# DI.net
KiCad netlist of a schematic drawn in Altium Designer
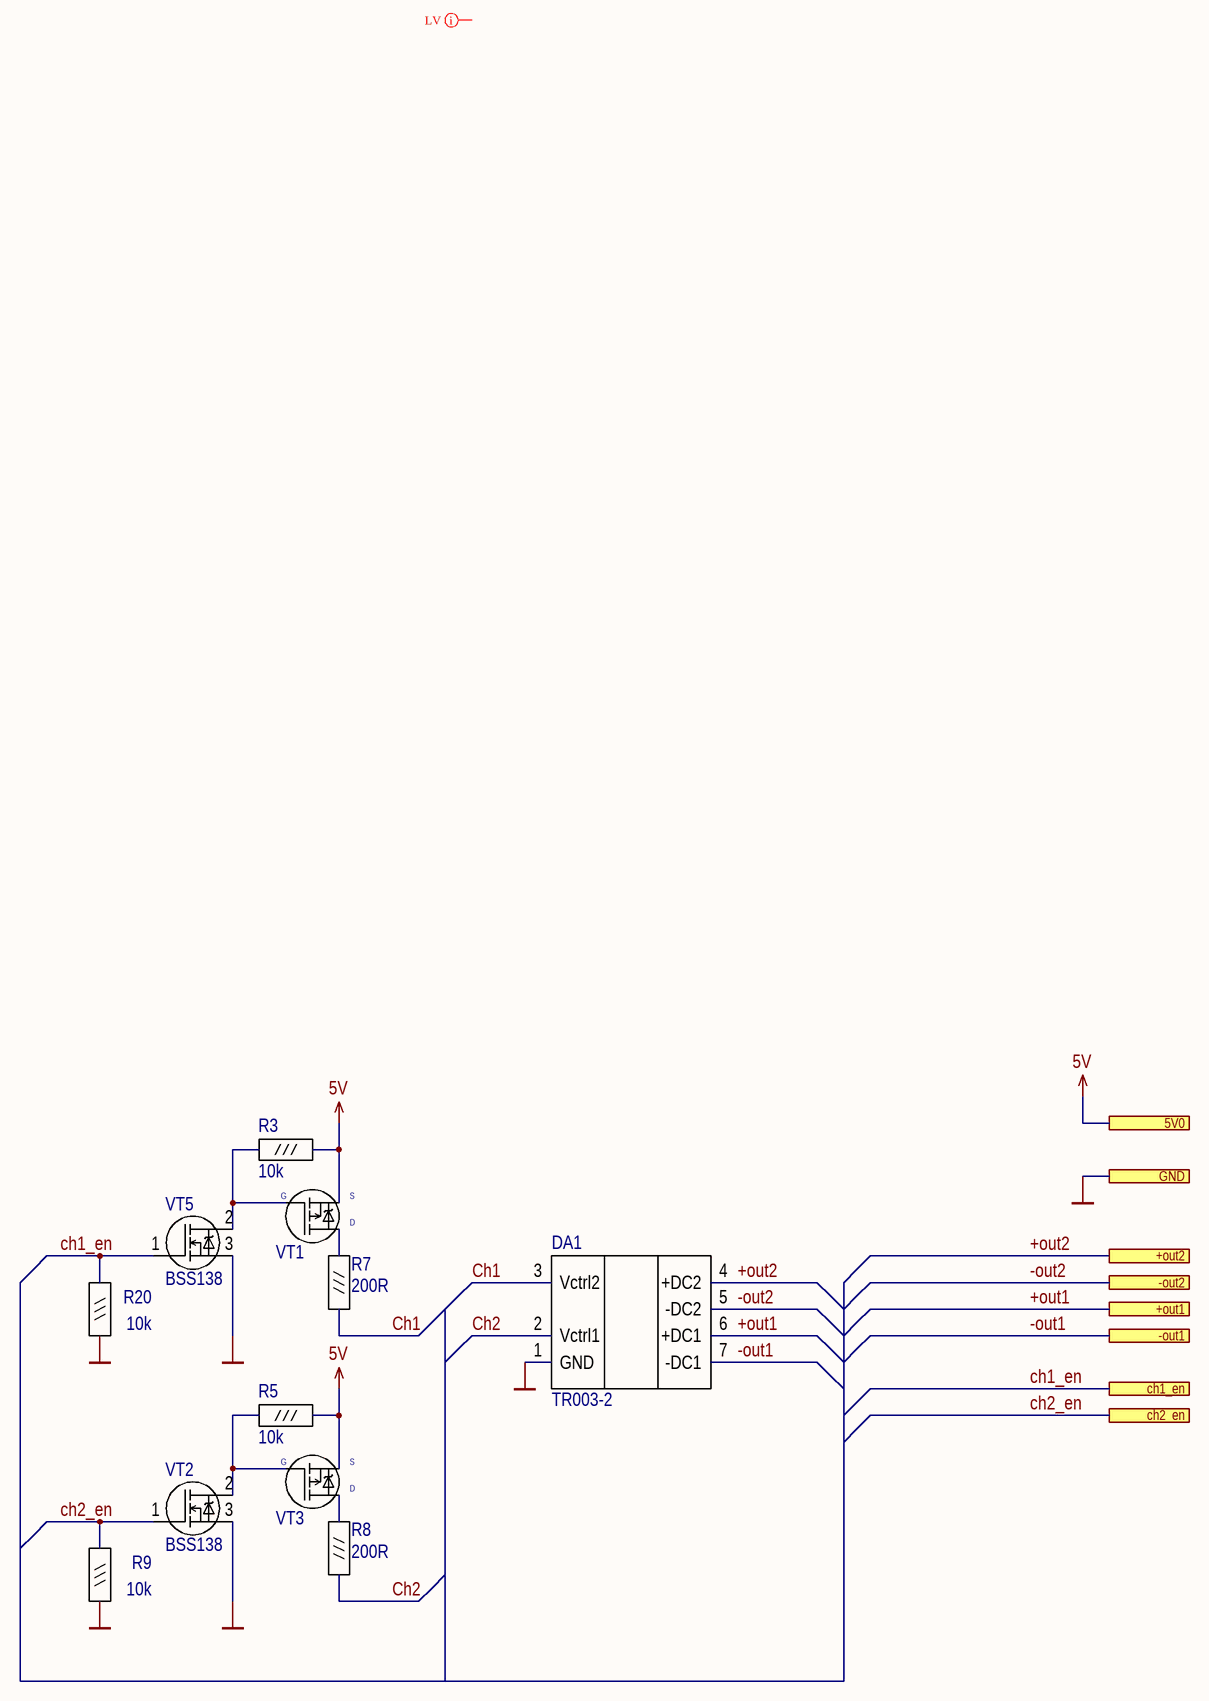
[diagram p0: DI.SchDoc]

(export (version "E")
  (design (tool "Eeschema 10.0.6"))
  (components
    (comp (ref "DA1") (value "TR003-2") (footprint "TR003-2") (libsource (lib "DB_IC") (part "TR003-2")))
    (comp (ref "R3")
      (value "10k")
      (footprint "R0603")
      (description "10 kOhms ±5% 0.1W, 1/10W Chip Resistor 0603 (1608 Metric) Moisture Resistant Thick Film")
      (fields (field (name "MPN") "RC0603JR-0710kL") (field (name "TOLERANCE") "5%"))
      (libsource (lib "DB_res_cap_ind") (part "R0603"))
    )
    (comp (ref "R5")
      (value "10k")
      (footprint "R0603")
      (description "10 kOhms ±5% 0.1W, 1/10W Chip Resistor 0603 (1608 Metric) Moisture Resistant Thick Film")
      (fields (field (name "MPN") "RC0603JR-0710kL") (field (name "TOLERANCE") "5%"))
      (libsource (lib "DB_res_cap_ind") (part "R0603"))
    )
    (comp (ref "R7")
      (value "200R")
      (footprint "R0603")
      (description "200 Ohms ±5% 0.1W, 1/10W Chip Resistor 0603 (1608 Metric) Moisture Resistant Thick Film")
      (fields (field (name "MPN") "RC0603JR-07200RL") (field (name "TOLERANCE") "5%"))
      (libsource (lib "DB_res_cap_ind") (part "R0603"))
    )
    (comp (ref "R8")
      (value "200R")
      (footprint "R0603")
      (description "200 Ohms ±5% 0.1W, 1/10W Chip Resistor 0603 (1608 Metric) Moisture Resistant Thick Film")
      (fields (field (name "MPN") "RC0603JR-07200RL") (field (name "TOLERANCE") "5%"))
      (libsource (lib "DB_res_cap_ind") (part "R0603"))
    )
    (comp (ref "R9")
      (value "10k")
      (footprint "R0603")
      (description "10 kOhms ±5% 0.1W, 1/10W Chip Resistor 0603 (1608 Metric) Moisture Resistant Thick Film")
      (fields (field (name "MPN") "RC0603JR-0710kL") (field (name "TOLERANCE") "5%"))
      (libsource (lib "DB_res_cap_ind") (part "R0603"))
    )
    (comp (ref "R20")
      (value "10k")
      (footprint "R0603")
      (description "10 kOhms ±5% 0.1W, 1/10W Chip Resistor 0603 (1608 Metric) Moisture Resistant Thick Film")
      (fields (field (name "MPN") "RC0603JR-0710kL") (field (name "TOLERANCE") "5%"))
      (libsource (lib "DB_res_cap_ind") (part "R0603"))
    )
    (comp (ref "VT1")
      (value "AO3401A")
      (footprint "sot23-3")
      (description "P-Channel 30V 4A (Ta) 1.4W (Ta) Surface Mount SOT-23-3L")
      (fields (field (name "MANUFACTURER") "Infineon Technologies"))
      (libsource (lib "DB_the_rest") (part "P_CH3"))
    )
    (comp (ref "VT2")
      (value "BSS138")
      (footprint "SOT23-3")
      (description "N-Channel 50V 200mA (Ta) 300mW (Ta) Surface Mount SOT-23-3")
      (fields (field (name "MANUFACTURER") "Diodes Incorporated"))
      (libsource (lib "DB_the_rest") (part "N_CH_GSD"))
    )
    (comp (ref "VT3")
      (value "AO3401A")
      (footprint "sot23-3")
      (description "P-Channel 30V 4A (Ta) 1.4W (Ta) Surface Mount SOT-23-3L")
      (fields (field (name "MANUFACTURER") "Infineon Technologies"))
      (libsource (lib "DB_the_rest") (part "P_CH3"))
    )
    (comp (ref "VT5")
      (value "BSS138")
      (footprint "SOT23-3")
      (description "N-Channel 50V 200mA (Ta) 300mW (Ta) Surface Mount SOT-23-3")
      (fields (field (name "MANUFACTURER") "Diodes Incorporated"))
      (libsource (lib "DB_the_rest") (part "N_CH_GSD"))
    )
  )
  (nets
    (net (code "1") (name "/+out1") (class "Default")
      (node (ref "DA1") (pin "6") (pinfunction "+DC1_6") (pintype "passive"))
    )
    (net (code "2") (name "/+out2") (class "Default")
      (node (ref "DA1") (pin "4") (pinfunction "+DC2_4") (pintype "passive"))
    )
    (net (code "3") (name "/-out1") (class "Default")
      (node (ref "DA1") (pin "7") (pinfunction "-DC1_7") (pintype "passive"))
    )
    (net (code "4") (name "/-out2") (class "Default")
      (node (ref "DA1") (pin "5") (pinfunction "-DC2_5") (pintype "passive"))
    )
    (net (code "5") (name "/Ch1") (class "Default")
      (node (ref "DA1") (pin "3") (pinfunction "Vctrl2_3") (pintype "passive"))
      (node (ref "R7") (pin "1") (pinfunction "1_1") (pintype "passive"))
    )
    (net (code "6") (name "/Ch2") (class "Default")
      (node (ref "DA1") (pin "2") (pinfunction "Vctrl1_2") (pintype "passive"))
      (node (ref "R8") (pin "1") (pinfunction "1_1") (pintype "passive"))
    )
    (net (code "7") (name "/ch1_en") (class "Default")
      (node (ref "R20") (pin "2") (pinfunction "2_2") (pintype "passive"))
      (node (ref "VT5") (pin "1") (pinfunction "G_1") (pintype "passive"))
    )
    (net (code "8") (name "/ch2_en") (class "Default")
      (node (ref "R9") (pin "2") (pinfunction "2_2") (pintype "passive"))
      (node (ref "VT2") (pin "1") (pinfunction "G_1") (pintype "passive"))
    )
    (net (code "9") (name "5V") (class "Default")
      (node (ref "R3") (pin "1") (pinfunction "1_1") (pintype "passive"))
      (node (ref "R5") (pin "1") (pinfunction "1_1") (pintype "passive"))
      (node (ref "VT1") (pin "2") (pinfunction "S_2") (pintype "passive"))
      (node (ref "VT3") (pin "2") (pinfunction "S_2") (pintype "passive"))
    )
    (net (code "10") (name "GND") (class "Default")
      (node (ref "DA1") (pin "1") (pinfunction "GND_1") (pintype "passive"))
      (node (ref "R20") (pin "1") (pinfunction "1_1") (pintype "passive"))
      (node (ref "R9") (pin "1") (pinfunction "1_1") (pintype "passive"))
      (node (ref "VT2") (pin "3") (pinfunction "S_3") (pintype "passive"))
      (node (ref "VT5") (pin "3") (pinfunction "S_3") (pintype "passive"))
    )
    (net (code "11") (name "Net-(VT1-D)") (class "Default")
      (node (ref "R7") (pin "2") (pinfunction "2_2") (pintype "passive"))
      (node (ref "VT1") (pin "3") (pinfunction "D_3") (pintype "passive"))
    )
    (net (code "12") (name "Net-(VT1-G)") (class "Default")
      (node (ref "R3") (pin "2") (pinfunction "2_2") (pintype "passive"))
      (node (ref "VT1") (pin "1") (pinfunction "G_1") (pintype "passive"))
      (node (ref "VT5") (pin "2") (pinfunction "D_2") (pintype "passive"))
    )
    (net (code "13") (name "Net-(VT2-D)") (class "Default")
      (node (ref "R5") (pin "2") (pinfunction "2_2") (pintype "passive"))
      (node (ref "VT2") (pin "2") (pinfunction "D_2") (pintype "passive"))
      (node (ref "VT3") (pin "1") (pinfunction "G_1") (pintype "passive"))
    )
    (net (code "14") (name "Net-(VT3-D)") (class "Default")
      (node (ref "R8") (pin "2") (pinfunction "2_2") (pintype "passive"))
      (node (ref "VT3") (pin "3") (pinfunction "D_3") (pintype "passive"))
    )
  )
)
